# MCU.net
KiCad netlist of a schematic drawn in Altium Designer
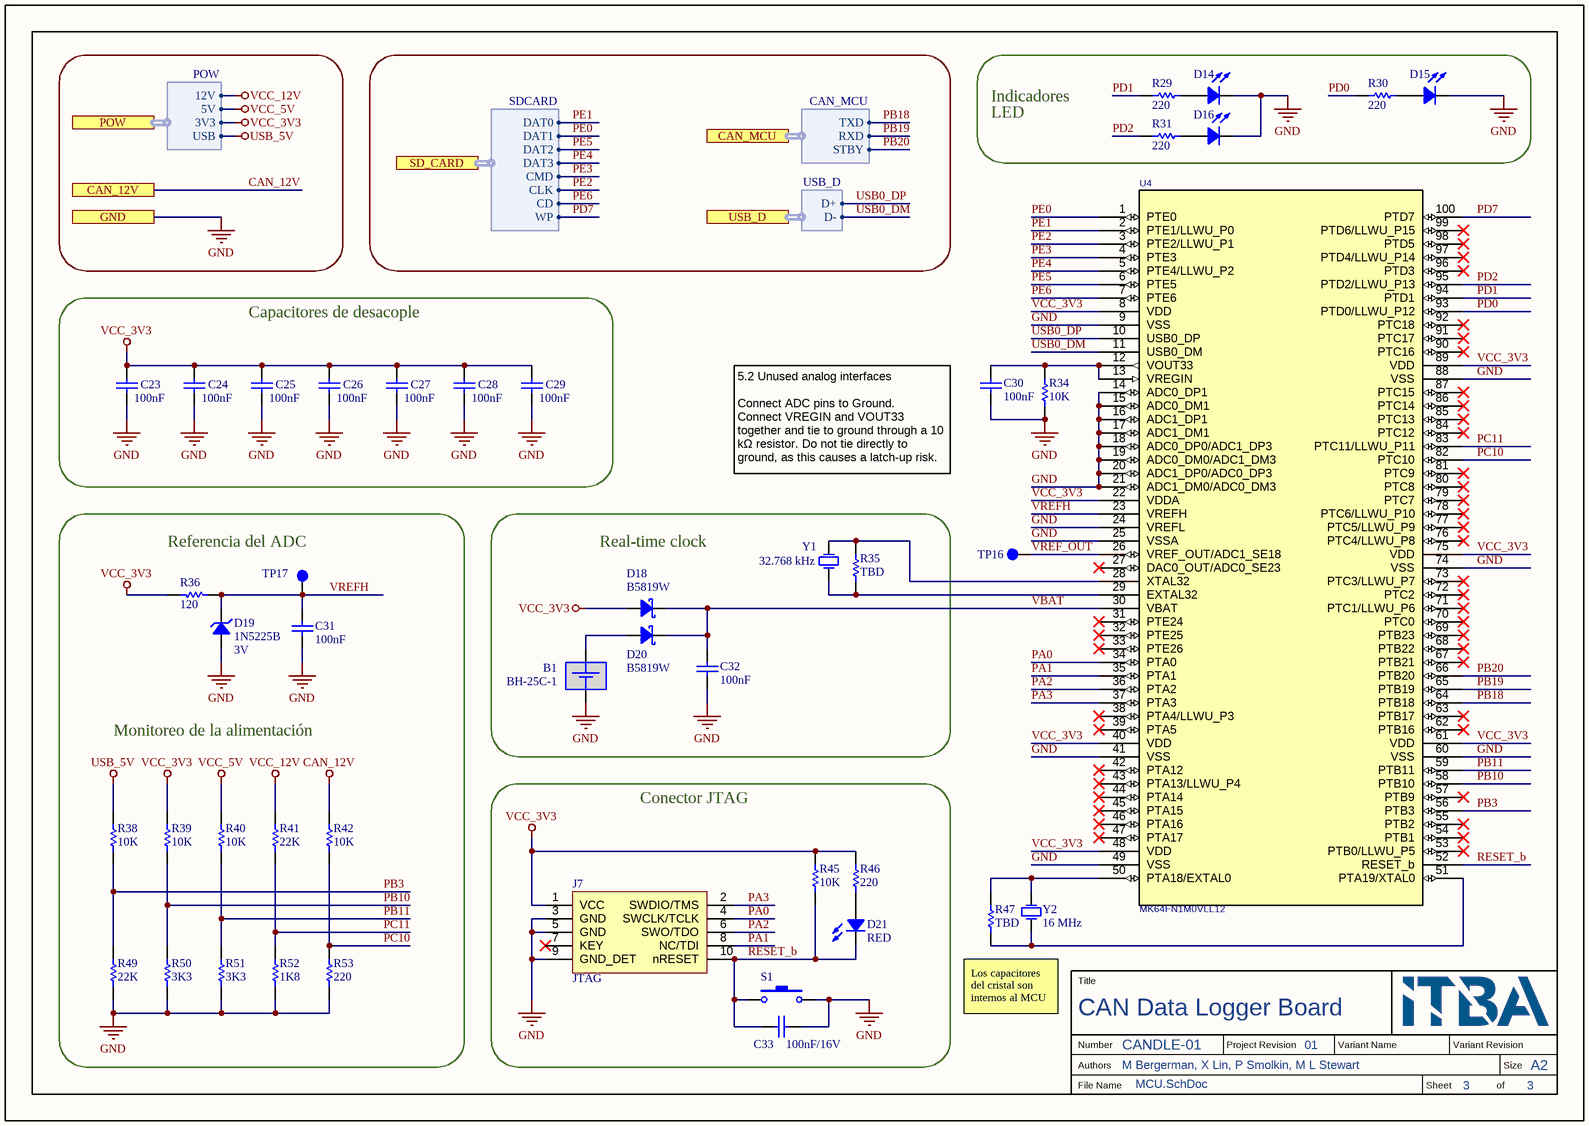
[diagram p0: MCU.SchDoc]

(export (version "E")
  (design (tool "Eeschema 10.0.6"))
  (components
    (comp (ref "B1")
      (value "BH-25C-1")
      (footprint "COIN_CELL_HOLDER")
      (description "Battery Holder")
      (libsource (lib "CANDLE-LIB") (part "Battery Holder"))
    )
    (comp (ref "C23")
      (value "100nF")
      (footprint "CAP0805")
      (description "SMD 0805 Capacitor")
      (libsource (lib "CANDLE-LIB") (part "Capacitor"))
    )
    (comp (ref "C24")
      (value "100nF")
      (footprint "CAP0805")
      (description "SMD 0805 Capacitor")
      (libsource (lib "CANDLE-LIB") (part "Capacitor"))
    )
    (comp (ref "C25")
      (value "100nF")
      (footprint "CAP0805")
      (description "SMD 0805 Capacitor")
      (libsource (lib "CANDLE-LIB") (part "Capacitor"))
    )
    (comp (ref "C26")
      (value "100nF")
      (footprint "CAP0805")
      (description "SMD 0805 Capacitor")
      (libsource (lib "CANDLE-LIB") (part "Capacitor"))
    )
    (comp (ref "C27")
      (value "100nF")
      (footprint "CAP0805")
      (description "SMD 0805 Capacitor")
      (libsource (lib "CANDLE-LIB") (part "Capacitor"))
    )
    (comp (ref "C28")
      (value "100nF")
      (footprint "CAP0805")
      (description "SMD 0805 Capacitor")
      (libsource (lib "CANDLE-LIB") (part "Capacitor"))
    )
    (comp (ref "C29")
      (value "100nF")
      (footprint "CAP0805")
      (description "SMD 0805 Capacitor")
      (libsource (lib "CANDLE-LIB") (part "Capacitor"))
    )
    (comp (ref "C30")
      (value "100nF")
      (footprint "CAP0805")
      (description "SMD 0805 Capacitor")
      (libsource (lib "CANDLE-LIB") (part "Capacitor"))
    )
    (comp (ref "C31")
      (value "100nF")
      (footprint "CAP0805")
      (description "SMD 0805 Capacitor")
      (libsource (lib "CANDLE-LIB") (part "Capacitor"))
    )
    (comp (ref "C32")
      (value "100nF")
      (footprint "CAP0805")
      (description "SMD 0805 Capacitor")
      (libsource (lib "CANDLE-LIB") (part "Capacitor"))
    )
    (comp (ref "C33")
      (value "100nF/16V")
      (footprint "CAP0805")
      (description "SMD 0805 Capacitor")
      (libsource (lib "CANDLE-LIB") (part "Capacitor"))
    )
    (comp (ref "D14")
      (value "RED")
      (footprint "LED-3MM-RED-RA")
      (description "Red 3mm LED")
      (libsource (lib "CANDLE-LIB") (part "LED 3mm Red RA"))
    )
    (comp (ref "D15")
      (value "RED")
      (footprint "LED-3MM-RED-RA")
      (description "Red 3mm LED")
      (libsource (lib "CANDLE-LIB") (part "LED 3mm Red RA"))
    )
    (comp (ref "D16")
      (value "RED")
      (footprint "LED-3MM-RED-RA")
      (description "Red 3mm LED")
      (libsource (lib "CANDLE-LIB") (part "LED 3mm Red RA"))
    )
    (comp (ref "D18")
      (value "B5819W")
      (footprint "SOD-123")
      (description "Schottky Diode")
      (libsource (lib "CANDLE-LIB") (part "Diode Schottky"))
    )
    (comp (ref "D19")
      (value "1N5225B")
      (footprint "DO-35")
      (description "Zener Diode")
      (fields (field (name "VOLTAGE") "3V"))
      (libsource (lib "CANDLE-LIB") (part "Diode Zener"))
    )
    (comp (ref "D20")
      (value "B5819W")
      (footprint "SOD-123")
      (description "Schottky Diode")
      (libsource (lib "CANDLE-LIB") (part "Diode Schottky"))
    )
    (comp (ref "D21")
      (value "RED")
      (footprint "LED-3MM-RED-RA")
      (description "Red 3mm LED")
      (libsource (lib "CANDLE-LIB") (part "LED 3mm Red RA"))
    )
    (comp (ref "J7")
      (value "JTAG")
      (footprint "JTAG-10PIN")
      (description "JTAG header")
      (libsource (lib "CANDLE-LIB") (part "JTAG Header"))
    )
    (comp (ref "R29")
      (value "220")
      (footprint "RES0805")
      (description "SMD 0805 Resistor")
      (libsource (lib "CANDLE-LIB") (part "Resistor"))
    )
    (comp (ref "R30")
      (value "220")
      (footprint "RES0805")
      (description "SMD 0805 Resistor")
      (libsource (lib "CANDLE-LIB") (part "Resistor"))
    )
    (comp (ref "R31")
      (value "220")
      (footprint "RES0805")
      (description "SMD 0805 Resistor")
      (libsource (lib "CANDLE-LIB") (part "Resistor"))
    )
    (comp (ref "R34")
      (value "10K")
      (footprint "RES0805")
      (description "SMD 0805 Resistor")
      (libsource (lib "CANDLE-LIB") (part "Resistor"))
    )
    (comp (ref "R35")
      (value "TBD")
      (footprint "RES0805")
      (description "SMD 0805 Resistor")
      (libsource (lib "CANDLE-LIB") (part "Resistor"))
    )
    (comp (ref "R36")
      (value "120")
      (footprint "RES0805")
      (description "SMD 0805 Resistor")
      (libsource (lib "CANDLE-LIB") (part "Resistor"))
    )
    (comp (ref "R38")
      (value "10K")
      (footprint "RES0805")
      (description "SMD 0805 Resistor")
      (libsource (lib "CANDLE-LIB") (part "Resistor"))
    )
    (comp (ref "R39")
      (value "10K")
      (footprint "RES0805")
      (description "SMD 0805 Resistor")
      (libsource (lib "CANDLE-LIB") (part "Resistor"))
    )
    (comp (ref "R40")
      (value "10K")
      (footprint "RES0805")
      (description "SMD 0805 Resistor")
      (libsource (lib "CANDLE-LIB") (part "Resistor"))
    )
    (comp (ref "R41")
      (value "22K")
      (footprint "RES0805")
      (description "SMD 0805 Resistor")
      (libsource (lib "CANDLE-LIB") (part "Resistor"))
    )
    (comp (ref "R42")
      (value "10K")
      (footprint "RES0805")
      (description "SMD 0805 Resistor")
      (libsource (lib "CANDLE-LIB") (part "Resistor"))
    )
    (comp (ref "R45")
      (value "10K")
      (footprint "RES0805")
      (description "SMD 0805 Resistor")
      (libsource (lib "CANDLE-LIB") (part "Resistor"))
    )
    (comp (ref "R46")
      (value "220")
      (footprint "RES0805")
      (description "SMD 0805 Resistor")
      (libsource (lib "CANDLE-LIB") (part "Resistor"))
    )
    (comp (ref "R47")
      (value "TBD")
      (footprint "RES0805")
      (description "SMD 0805 Resistor")
      (libsource (lib "CANDLE-LIB") (part "Resistor"))
    )
    (comp (ref "R49")
      (value "22K")
      (footprint "RES0805")
      (description "SMD 0805 Resistor")
      (libsource (lib "CANDLE-LIB") (part "Resistor"))
    )
    (comp (ref "R50")
      (value "3K3")
      (footprint "RES0805")
      (description "SMD 0805 Resistor")
      (libsource (lib "CANDLE-LIB") (part "Resistor"))
    )
    (comp (ref "R51")
      (value "3K3")
      (footprint "RES0805")
      (description "SMD 0805 Resistor")
      (libsource (lib "CANDLE-LIB") (part "Resistor"))
    )
    (comp (ref "R52")
      (value "1K8")
      (footprint "RES0805")
      (description "SMD 0805 Resistor")
      (libsource (lib "CANDLE-LIB") (part "Resistor"))
    )
    (comp (ref "R53")
      (value "220")
      (footprint "RES0805")
      (description "SMD 0805 Resistor")
      (libsource (lib "CANDLE-LIB") (part "Resistor"))
    )
    (comp (ref "S1")
      (value "Tact Switch")
      (footprint "TACT SWITCH")
      (description "2-pin 6mm tactile switch (push-button)")
      (fields (field (name "PUBLISHER") "Altium Limited"))
      (libsource (lib "CANDLE-LIB") (part "Tactile Switch"))
    )
    (comp (ref "TP16")
      (value "Testpoint")
      (footprint "TP_SMD_Ø1.0mm")
      (libsource (lib "CANDLE-LIB") (part "Testpoint"))
    )
    (comp (ref "TP17")
      (value "Testpoint")
      (footprint "TP_SMD_Ø1.0mm")
      (libsource (lib "CANDLE-LIB") (part "Testpoint"))
    )
    (comp (ref "U4")
      (value "MK64FN1M0VLL12")
      (footprint "QFP50P1600X1600X160-100N")
      (description "120 MHz ARM Cortex®-M4-based Microcontroller with FPU")
      (fields (field (name "MFG") "NXP") (field (name "FOOTPRINT CHECKED") "Assign OK, Footprint OK"))
      (libsource (lib "CANDLE-LIB") (part "MK64FN1M0VLL12_1"))
    )
    (comp (ref "Y1")
      (value "32.768 kHz")
      (footprint "XTAL-RAD-3X8")
      (description "Crystal Oscillator - Radial 3x8mm")
      (libsource (lib "CANDLE-LIB") (part "Crystal 32.768 kHz"))
    )
    (comp (ref "Y2")
      (value "16 MHz")
      (footprint "XTAL-HC-49S")
      (description "Crystal Oscillator HS-49S")
      (fields (field (name "PUBLISHER") "Altium Limited"))
      (libsource (lib "CANDLE-LIB") (part "Crystal 16 MHz"))
    )
  )
  (nets
    (net (code "5") (name "/PA0") (class "Default")
      (node (ref "J7") (pin "4") (pinfunction "SWCLK/TCLK_4") (pintype "passive"))
      (node (ref "U4") (pin "34") (pinfunction "PTA0_34") (pintype "bidirectional"))
    )
    (net (code "6") (name "/PA1") (class "Default")
      (node (ref "J7") (pin "8") (pinfunction "NC/TDI_8") (pintype "passive"))
      (node (ref "U4") (pin "35") (pinfunction "PTA1_35") (pintype "bidirectional"))
    )
    (net (code "7") (name "/PA2") (class "Default")
      (node (ref "J7") (pin "6") (pinfunction "SWO/TDO_6") (pintype "passive"))
      (node (ref "U4") (pin "36") (pinfunction "PTA2_36") (pintype "bidirectional"))
    )
    (net (code "8") (name "/PA3") (class "Default")
      (node (ref "J7") (pin "2") (pinfunction "SWDIO/TMS_2") (pintype "passive"))
      (node (ref "U4") (pin "37") (pinfunction "PTA3_37") (pintype "bidirectional"))
    )
    (net (code "9") (name "/PB3") (class "Default")
      (node (ref "R38") (pin "2") (pinfunction "2_2") (pintype "passive"))
      (node (ref "R49") (pin "1") (pinfunction "1_1") (pintype "passive"))
      (node (ref "U4") (pin "56") (pinfunction "PTB3_56") (pintype "bidirectional"))
    )
    (net (code "10") (name "/PB10") (class "Default")
      (node (ref "R39") (pin "2") (pinfunction "2_2") (pintype "passive"))
      (node (ref "R50") (pin "1") (pinfunction "1_1") (pintype "passive"))
      (node (ref "U4") (pin "58") (pinfunction "PTB10_58") (pintype "bidirectional"))
    )
    (net (code "11") (name "/PB11") (class "Default")
      (node (ref "R40") (pin "2") (pinfunction "2_2") (pintype "passive"))
      (node (ref "R51") (pin "1") (pinfunction "1_1") (pintype "passive"))
      (node (ref "U4") (pin "59") (pinfunction "PTB11_59") (pintype "bidirectional"))
    )
    (net (code "12") (name "/PB18") (class "Default")
      (node (ref "U4") (pin "64") (pinfunction "PTB18_64") (pintype "bidirectional"))
    )
    (net (code "13") (name "/PB19") (class "Default")
      (node (ref "U4") (pin "65") (pinfunction "PTB19_65") (pintype "bidirectional"))
    )
    (net (code "14") (name "/PB20") (class "Default")
      (node (ref "U4") (pin "66") (pinfunction "PTB20_66") (pintype "bidirectional"))
    )
    (net (code "15") (name "/PC10") (class "Default")
      (node (ref "R42") (pin "2") (pinfunction "2_2") (pintype "passive"))
      (node (ref "R53") (pin "1") (pinfunction "1_1") (pintype "passive"))
      (node (ref "U4") (pin "82") (pinfunction "PTC10_82") (pintype "bidirectional"))
    )
    (net (code "16") (name "/PC11") (class "Default")
      (node (ref "R41") (pin "2") (pinfunction "2_2") (pintype "passive"))
      (node (ref "R52") (pin "1") (pinfunction "1_1") (pintype "passive"))
      (node (ref "U4") (pin "83") (pinfunction "PTC11/LLWU_P11_83") (pintype "bidirectional"))
    )
    (net (code "17") (name "/PD0") (class "Default")
      (node (ref "R30") (pin "1") (pinfunction "1_1") (pintype "passive"))
      (node (ref "U4") (pin "93") (pinfunction "PTD0/LLWU_P12_93") (pintype "bidirectional"))
    )
    (net (code "18") (name "/PD1") (class "Default")
      (node (ref "R29") (pin "1") (pinfunction "1_1") (pintype "passive"))
      (node (ref "U4") (pin "94") (pinfunction "PTD1_94") (pintype "bidirectional"))
    )
    (net (code "19") (name "/PD2") (class "Default")
      (node (ref "R31") (pin "1") (pinfunction "1_1") (pintype "passive"))
      (node (ref "U4") (pin "95") (pinfunction "PTD2/LLWU_P13_95") (pintype "bidirectional"))
    )
    (net (code "20") (name "/PD7") (class "Default")
      (node (ref "U4") (pin "100") (pinfunction "PTD7_100") (pintype "bidirectional"))
    )
    (net (code "21") (name "/PE0") (class "Default")
      (node (ref "U4") (pin "1") (pinfunction "PTE0_1") (pintype "bidirectional"))
    )
    (net (code "22") (name "/PE1") (class "Default")
      (node (ref "U4") (pin "2") (pinfunction "PTE1/LLWU_P0_2") (pintype "bidirectional"))
    )
    (net (code "23") (name "/PE2") (class "Default")
      (node (ref "U4") (pin "3") (pinfunction "PTE2/LLWU_P1_3") (pintype "bidirectional"))
    )
    (net (code "24") (name "/PE3") (class "Default")
      (node (ref "U4") (pin "4") (pinfunction "PTE3_4") (pintype "bidirectional"))
    )
    (net (code "25") (name "/PE4") (class "Default")
      (node (ref "U4") (pin "5") (pinfunction "PTE4/LLWU_P2_5") (pintype "bidirectional"))
    )
    (net (code "26") (name "/PE5") (class "Default")
      (node (ref "U4") (pin "6") (pinfunction "PTE5_6") (pintype "bidirectional"))
    )
    (net (code "27") (name "/PE6") (class "Default")
      (node (ref "U4") (pin "7") (pinfunction "PTE6_7") (pintype "bidirectional"))
    )
    (net (code "28") (name "/RESET_b") (class "Default")
      (node (ref "C33") (pin "2") (pinfunction "2_2") (pintype "passive"))
      (node (ref "D21") (pin "2") (pinfunction "K_2") (pintype "passive"))
      (node (ref "J7") (pin "10") (pinfunction "nRESET_10") (pintype "passive"))
      (node (ref "R45") (pin "1") (pinfunction "1_1") (pintype "passive"))
      (node (ref "S1") (pin "1") (pinfunction "1_1") (pintype "passive"))
      (node (ref "U4") (pin "52") (pinfunction "RESET_b_52") (pintype "passive"))
    )
    (net (code "29") (name "/USB0_DM") (class "Default")
      (node (ref "U4") (pin "11") (pinfunction "USB0_DM_11") (pintype "passive"))
    )
    (net (code "30") (name "/USB0_DP") (class "Default")
      (node (ref "U4") (pin "10") (pinfunction "USB0_DP_10") (pintype "passive"))
    )
    (net (code "31") (name "/VBAT") (class "Default")
      (node (ref "C32") (pin "2") (pinfunction "2_2") (pintype "passive"))
      (node (ref "D18") (pin "2") (pinfunction "K_2") (pintype "passive"))
      (node (ref "D20") (pin "2") (pinfunction "K_2") (pintype "passive"))
      (node (ref "U4") (pin "30") (pinfunction "VBAT_30") (pintype "power_in"))
    )
    (net (code "32") (name "/VREFH") (class "Default")
      (node (ref "C31") (pin "2") (pinfunction "2_2") (pintype "passive"))
      (node (ref "D19") (pin "1") (pinfunction "K_1") (pintype "passive"))
      (node (ref "R36") (pin "1") (pinfunction "1_1") (pintype "passive"))
      (node (ref "TP17") (pin "1") (pinfunction "TP_1") (pintype "passive"))
      (node (ref "U4") (pin "23") (pinfunction "VREFH_23") (pintype "power_in"))
    )
    (net (code "33") (name "/VREF_OUT") (class "Default")
      (node (ref "TP16") (pin "1") (pinfunction "TP_1") (pintype "passive"))
      (node (ref "U4") (pin "26") (pinfunction "VREF_OUT/ADC1_SE18_26") (pintype "bidirectional"))
    )
    (net (code "38") (name "CAN_12V") (class "Default")
      (node (ref "R42") (pin "1") (pinfunction "1_1") (pintype "passive"))
    )
    (net (code "39") (name "GND") (class "Default")
      (node (ref "B1") (pin "2") (pinfunction "2_2") (pintype "passive"))
      (node (ref "C23") (pin "1") (pinfunction "1_1") (pintype "passive"))
      (node (ref "C24") (pin "1") (pinfunction "1_1") (pintype "passive"))
      (node (ref "C25") (pin "1") (pinfunction "1_1") (pintype "passive"))
      (node (ref "C26") (pin "1") (pinfunction "1_1") (pintype "passive"))
      (node (ref "C27") (pin "1") (pinfunction "1_1") (pintype "passive"))
      (node (ref "C28") (pin "1") (pinfunction "1_1") (pintype "passive"))
      (node (ref "C29") (pin "1") (pinfunction "1_1") (pintype "passive"))
      (node (ref "C30") (pin "1") (pinfunction "1_1") (pintype "passive"))
      (node (ref "C31") (pin "1") (pinfunction "1_1") (pintype "passive"))
      (node (ref "C32") (pin "1") (pinfunction "1_1") (pintype "passive"))
      (node (ref "C33") (pin "1") (pinfunction "1_1") (pintype "passive"))
      (node (ref "D14") (pin "2") (pinfunction "K_2") (pintype "passive"))
      (node (ref "D15") (pin "2") (pinfunction "K_2") (pintype "passive"))
      (node (ref "D16") (pin "2") (pinfunction "K_2") (pintype "passive"))
      (node (ref "D19") (pin "2") (pinfunction "A_2") (pintype "passive"))
      (node (ref "J7") (pin "3") (pinfunction "GND_3") (pintype "passive"))
      (node (ref "J7") (pin "5") (pinfunction "GND_5") (pintype "passive"))
      (node (ref "J7") (pin "9") (pinfunction "GND_DET_9") (pintype "passive"))
      (node (ref "R34") (pin "1") (pinfunction "1_1") (pintype "passive"))
      (node (ref "R49") (pin "2") (pinfunction "2_2") (pintype "passive"))
      (node (ref "R50") (pin "2") (pinfunction "2_2") (pintype "passive"))
      (node (ref "R51") (pin "2") (pinfunction "2_2") (pintype "passive"))
      (node (ref "R52") (pin "2") (pinfunction "2_2") (pintype "passive"))
      (node (ref "R53") (pin "2") (pinfunction "2_2") (pintype "passive"))
      (node (ref "S1") (pin "2") (pinfunction "2_2") (pintype "passive"))
      (node (ref "U4") (pin "14") (pinfunction "ADC0_DP1_14") (pintype "bidirectional"))
      (node (ref "U4") (pin "15") (pinfunction "ADC0_DM1_15") (pintype "bidirectional"))
      (node (ref "U4") (pin "16") (pinfunction "ADC1_DP1_16") (pintype "bidirectional"))
      (node (ref "U4") (pin "17") (pinfunction "ADC1_DM1_17") (pintype "bidirectional"))
      (node (ref "U4") (pin "18") (pinfunction "ADC0_DP0/ADC1_DP3_18") (pintype "bidirectional"))
      (node (ref "U4") (pin "19") (pinfunction "ADC0_DM0/ADC1_DM3_19") (pintype "bidirectional"))
      (node (ref "U4") (pin "20") (pinfunction "ADC1_DP0/ADC0_DP3_20") (pintype "bidirectional"))
      (node (ref "U4") (pin "21") (pinfunction "ADC1_DM0/ADC0_DM3_21") (pintype "bidirectional"))
      (node (ref "U4") (pin "24") (pinfunction "VREFL_24") (pintype "power_in"))
      (node (ref "U4") (pin "25") (pinfunction "VSSA_25") (pintype "power_in"))
      (node (ref "U4") (pin "41") (pinfunction "VSS_41") (pintype "power_in"))
      (node (ref "U4") (pin "49") (pinfunction "VSS_49") (pintype "power_in"))
      (node (ref "U4") (pin "60") (pinfunction "VSS_60") (pintype "power_in"))
      (node (ref "U4") (pin "74") (pinfunction "VSS_74") (pintype "power_in"))
      (node (ref "U4") (pin "88") (pinfunction "VSS_88") (pintype "power_in"))
      (node (ref "U4") (pin "9") (pinfunction "VSS_9") (pintype "power_in"))
    )
    (net (code "40") (name "Net-(D14-A)") (class "Default")
      (node (ref "D14") (pin "1") (pinfunction "A_1") (pintype "passive"))
      (node (ref "R29") (pin "2") (pinfunction "2_2") (pintype "passive"))
    )
    (net (code "41") (name "Net-(D15-A)") (class "Default")
      (node (ref "D15") (pin "1") (pinfunction "A_1") (pintype "passive"))
      (node (ref "R30") (pin "2") (pinfunction "2_2") (pintype "passive"))
    )
    (net (code "42") (name "Net-(D16-A)") (class "Default")
      (node (ref "D16") (pin "1") (pinfunction "A_1") (pintype "passive"))
      (node (ref "R31") (pin "2") (pinfunction "2_2") (pintype "passive"))
    )
    (net (code "43") (name "Net-(D20-A)") (class "Default")
      (node (ref "B1") (pin "1") (pinfunction "1_1") (pintype "passive"))
      (node (ref "D20") (pin "1") (pinfunction "A_1") (pintype "passive"))
    )
    (net (code "44") (name "Net-(D21-A)") (class "Default")
      (node (ref "D21") (pin "1") (pinfunction "A_1") (pintype "passive"))
      (node (ref "R46") (pin "2") (pinfunction "2_2") (pintype "passive"))
    )
    (net (code "45") (name "Net-(U4-EXTAL32)") (class "Default")
      (node (ref "R35") (pin "2") (pinfunction "2_2") (pintype "passive"))
      (node (ref "U4") (pin "29") (pinfunction "EXTAL32_29") (pintype "passive"))
      (node (ref "Y1") (pin "1") (pinfunction "OSC1_1") (pintype "passive"))
    )
    (net (code "46") (name "Net-(U4-PTA18{slash}EXTAL0)") (class "Default")
      (node (ref "R47") (pin "2") (pinfunction "2_2") (pintype "passive"))
      (node (ref "U4") (pin "50") (pinfunction "PTA18/EXTAL0_50") (pintype "bidirectional"))
      (node (ref "Y2") (pin "2") (pinfunction "OSC2_2") (pintype "passive"))
    )
    (net (code "47") (name "Net-(U4-PTA19{slash}XTAL0)") (class "Default")
      (node (ref "R47") (pin "1") (pinfunction "1_1") (pintype "passive"))
      (node (ref "U4") (pin "51") (pinfunction "PTA19/XTAL0_51") (pintype "bidirectional"))
      (node (ref "Y2") (pin "1") (pinfunction "OSC1_1") (pintype "passive"))
    )
    (net (code "48") (name "Net-(U4-VOUT33)") (class "Default")
      (node (ref "C30") (pin "2") (pinfunction "2_2") (pintype "passive"))
      (node (ref "R34") (pin "2") (pinfunction "2_2") (pintype "passive"))
      (node (ref "U4") (pin "12") (pinfunction "VOUT33_12") (pintype "output"))
      (node (ref "U4") (pin "13") (pinfunction "VREGIN_13") (pintype "input"))
    )
    (net (code "49") (name "Net-(U4-XTAL32)") (class "Default")
      (node (ref "R35") (pin "1") (pinfunction "1_1") (pintype "passive"))
      (node (ref "U4") (pin "28") (pinfunction "XTAL32_28") (pintype "passive"))
      (node (ref "Y1") (pin "2") (pinfunction "OSC2_2") (pintype "passive"))
    )
    (net (code "50") (name "USB_5V") (class "Default")
      (node (ref "R38") (pin "1") (pinfunction "1_1") (pintype "passive"))
    )
    (net (code "51") (name "VCC_3V3") (class "Default")
      (node (ref "C23") (pin "2") (pinfunction "2_2") (pintype "passive"))
      (node (ref "C24") (pin "2") (pinfunction "2_2") (pintype "passive"))
      (node (ref "C25") (pin "2") (pinfunction "2_2") (pintype "passive"))
      (node (ref "C26") (pin "2") (pinfunction "2_2") (pintype "passive"))
      (node (ref "C27") (pin "2") (pinfunction "2_2") (pintype "passive"))
      (node (ref "C28") (pin "2") (pinfunction "2_2") (pintype "passive"))
      (node (ref "C29") (pin "2") (pinfunction "2_2") (pintype "passive"))
      (node (ref "D18") (pin "1") (pinfunction "A_1") (pintype "passive"))
      (node (ref "J7") (pin "1") (pinfunction "VCC_1") (pintype "passive"))
      (node (ref "R36") (pin "2") (pinfunction "2_2") (pintype "passive"))
      (node (ref "R39") (pin "1") (pinfunction "1_1") (pintype "passive"))
      (node (ref "R45") (pin "2") (pinfunction "2_2") (pintype "passive"))
      (node (ref "R46") (pin "1") (pinfunction "1_1") (pintype "passive"))
      (node (ref "U4") (pin "22") (pinfunction "VDDA_22") (pintype "power_in"))
      (node (ref "U4") (pin "40") (pinfunction "VDD_40") (pintype "power_in"))
      (node (ref "U4") (pin "48") (pinfunction "VDD_48") (pintype "power_in"))
      (node (ref "U4") (pin "61") (pinfunction "VDD_61") (pintype "power_in"))
      (node (ref "U4") (pin "75") (pinfunction "VDD_75") (pintype "power_in"))
      (node (ref "U4") (pin "8") (pinfunction "VDD_8") (pintype "power_in"))
      (node (ref "U4") (pin "89") (pinfunction "VDD_89") (pintype "power_in"))
    )
    (net (code "52") (name "VCC_5V") (class "Default")
      (node (ref "R40") (pin "1") (pinfunction "1_1") (pintype "passive"))
    )
    (net (code "53") (name "VCC_12V") (class "Default")
      (node (ref "R41") (pin "1") (pinfunction "1_1") (pintype "passive"))
    )
    (net (code "54") (name "unconnected-(J7-KEY-Pad7)") (class "Default")
      (node (ref "J7") (pin "7") (pinfunction "KEY_7") (pintype "passive+no_connect"))
    )
    (net (code "55") (name "unconnected-(U4-DAC0_OUT{slash}ADC0_SE23-Pad27)") (class "Default")
      (node (ref "U4") (pin "27") (pinfunction "DAC0_OUT/ADC0_SE23_27") (pintype "bidirectional+no_connect"))
    )
    (net (code "56") (name "unconnected-(U4-PTA4{slash}LLWU_P3-Pad38)") (class "Default")
      (node (ref "U4") (pin "38") (pinfunction "PTA4/LLWU_P3_38") (pintype "bidirectional+no_connect"))
    )
    (net (code "57") (name "unconnected-(U4-PTA5-Pad39)") (class "Default")
      (node (ref "U4") (pin "39") (pinfunction "PTA5_39") (pintype "bidirectional+no_connect"))
    )
    (net (code "58") (name "unconnected-(U4-PTA12-Pad42)") (class "Default")
      (node (ref "U4") (pin "42") (pinfunction "PTA12_42") (pintype "bidirectional+no_connect"))
    )
    (net (code "59") (name "unconnected-(U4-PTA13{slash}LLWU_P4-Pad43)") (class "Default")
      (node (ref "U4") (pin "43") (pinfunction "PTA13/LLWU_P4_43") (pintype "bidirectional+no_connect"))
    )
    (net (code "60") (name "unconnected-(U4-PTA14-Pad44)") (class "Default")
      (node (ref "U4") (pin "44") (pinfunction "PTA14_44") (pintype "bidirectional+no_connect"))
    )
    (net (code "61") (name "unconnected-(U4-PTA15-Pad45)") (class "Default")
      (node (ref "U4") (pin "45") (pinfunction "PTA15_45") (pintype "bidirectional+no_connect"))
    )
    (net (code "62") (name "unconnected-(U4-PTA16-Pad46)") (class "Default")
      (node (ref "U4") (pin "46") (pinfunction "PTA16_46") (pintype "bidirectional+no_connect"))
    )
    (net (code "63") (name "unconnected-(U4-PTA17-Pad47)") (class "Default")
      (node (ref "U4") (pin "47") (pinfunction "PTA17_47") (pintype "bidirectional+no_connect"))
    )
    (net (code "64") (name "unconnected-(U4-PTB0{slash}LLWU_P5-Pad53)") (class "Default")
      (node (ref "U4") (pin "53") (pinfunction "PTB0/LLWU_P5_53") (pintype "bidirectional+no_connect"))
    )
    (net (code "65") (name "unconnected-(U4-PTB1-Pad54)") (class "Default")
      (node (ref "U4") (pin "54") (pinfunction "PTB1_54") (pintype "bidirectional+no_connect"))
    )
    (net (code "66") (name "unconnected-(U4-PTB2-Pad55)") (class "Default")
      (node (ref "U4") (pin "55") (pinfunction "PTB2_55") (pintype "bidirectional+no_connect"))
    )
    (net (code "67") (name "unconnected-(U4-PTB9-Pad57)") (class "Default")
      (node (ref "U4") (pin "57") (pinfunction "PTB9_57") (pintype "bidirectional+no_connect"))
    )
    (net (code "68") (name "unconnected-(U4-PTB16-Pad62)") (class "Default")
      (node (ref "U4") (pin "62") (pinfunction "PTB16_62") (pintype "bidirectional+no_connect"))
    )
    (net (code "69") (name "unconnected-(U4-PTB17-Pad63)") (class "Default")
      (node (ref "U4") (pin "63") (pinfunction "PTB17_63") (pintype "bidirectional+no_connect"))
    )
    (net (code "70") (name "unconnected-(U4-PTB21-Pad67)") (class "Default")
      (node (ref "U4") (pin "67") (pinfunction "PTB21_67") (pintype "bidirectional+no_connect"))
    )
    (net (code "71") (name "unconnected-(U4-PTB22-Pad68)") (class "Default")
      (node (ref "U4") (pin "68") (pinfunction "PTB22_68") (pintype "bidirectional+no_connect"))
    )
    (net (code "72") (name "unconnected-(U4-PTB23-Pad69)") (class "Default")
      (node (ref "U4") (pin "69") (pinfunction "PTB23_69") (pintype "bidirectional+no_connect"))
    )
    (net (code "73") (name "unconnected-(U4-PTC0-Pad70)") (class "Default")
      (node (ref "U4") (pin "70") (pinfunction "PTC0_70") (pintype "bidirectional+no_connect"))
    )
    (net (code "74") (name "unconnected-(U4-PTC1{slash}LLWU_P6-Pad71)") (class "Default")
      (node (ref "U4") (pin "71") (pinfunction "PTC1/LLWU_P6_71") (pintype "bidirectional+no_connect"))
    )
    (net (code "75") (name "unconnected-(U4-PTC2-Pad72)") (class "Default")
      (node (ref "U4") (pin "72") (pinfunction "PTC2_72") (pintype "bidirectional+no_connect"))
    )
    (net (code "76") (name "unconnected-(U4-PTC3{slash}LLWU_P7-Pad73)") (class "Default")
      (node (ref "U4") (pin "73") (pinfunction "PTC3/LLWU_P7_73") (pintype "bidirectional+no_connect"))
    )
    (net (code "77") (name "unconnected-(U4-PTC4{slash}LLWU_P8-Pad76)") (class "Default")
      (node (ref "U4") (pin "76") (pinfunction "PTC4/LLWU_P8_76") (pintype "bidirectional+no_connect"))
    )
    (net (code "78") (name "unconnected-(U4-PTC5{slash}LLWU_P9-Pad77)") (class "Default")
      (node (ref "U4") (pin "77") (pinfunction "PTC5/LLWU_P9_77") (pintype "bidirectional+no_connect"))
    )
    (net (code "79") (name "unconnected-(U4-PTC6{slash}LLWU_P10-Pad78)") (class "Default")
      (node (ref "U4") (pin "78") (pinfunction "PTC6/LLWU_P10_78") (pintype "bidirectional+no_connect"))
    )
    (net (code "80") (name "unconnected-(U4-PTC7-Pad79)") (class "Default")
      (node (ref "U4") (pin "79") (pinfunction "PTC7_79") (pintype "bidirectional+no_connect"))
    )
    (net (code "81") (name "unconnected-(U4-PTC8-Pad80)") (class "Default")
      (node (ref "U4") (pin "80") (pinfunction "PTC8_80") (pintype "bidirectional+no_connect"))
    )
    (net (code "82") (name "unconnected-(U4-PTC9-Pad81)") (class "Default")
      (node (ref "U4") (pin "81") (pinfunction "PTC9_81") (pintype "bidirectional+no_connect"))
    )
    (net (code "83") (name "unconnected-(U4-PTC12-Pad84)") (class "Default")
      (node (ref "U4") (pin "84") (pinfunction "PTC12_84") (pintype "bidirectional+no_connect"))
    )
    (net (code "84") (name "unconnected-(U4-PTC13-Pad85)") (class "Default")
      (node (ref "U4") (pin "85") (pinfunction "PTC13_85") (pintype "bidirectional+no_connect"))
    )
    (net (code "85") (name "unconnected-(U4-PTC14-Pad86)") (class "Default")
      (node (ref "U4") (pin "86") (pinfunction "PTC14_86") (pintype "bidirectional+no_connect"))
    )
    (net (code "86") (name "unconnected-(U4-PTC15-Pad87)") (class "Default")
      (node (ref "U4") (pin "87") (pinfunction "PTC15_87") (pintype "bidirectional+no_connect"))
    )
    (net (code "87") (name "unconnected-(U4-PTC16-Pad90)") (class "Default")
      (node (ref "U4") (pin "90") (pinfunction "PTC16_90") (pintype "bidirectional+no_connect"))
    )
    (net (code "88") (name "unconnected-(U4-PTC17-Pad91)") (class "Default")
      (node (ref "U4") (pin "91") (pinfunction "PTC17_91") (pintype "bidirectional+no_connect"))
    )
    (net (code "89") (name "unconnected-(U4-PTC18-Pad92)") (class "Default")
      (node (ref "U4") (pin "92") (pinfunction "PTC18_92") (pintype "bidirectional+no_connect"))
    )
    (net (code "90") (name "unconnected-(U4-PTD3-Pad96)") (class "Default")
      (node (ref "U4") (pin "96") (pinfunction "PTD3_96") (pintype "bidirectional+no_connect"))
    )
    (net (code "91") (name "unconnected-(U4-PTD4{slash}LLWU_P14-Pad97)") (class "Default")
      (node (ref "U4") (pin "97") (pinfunction "PTD4/LLWU_P14_97") (pintype "bidirectional+no_connect"))
    )
    (net (code "92") (name "unconnected-(U4-PTD5-Pad98)") (class "Default")
      (node (ref "U4") (pin "98") (pinfunction "PTD5_98") (pintype "bidirectional+no_connect"))
    )
    (net (code "93") (name "unconnected-(U4-PTD6{slash}LLWU_P15-Pad99)") (class "Default")
      (node (ref "U4") (pin "99") (pinfunction "PTD6/LLWU_P15_99") (pintype "bidirectional+no_connect"))
    )
    (net (code "94") (name "unconnected-(U4-PTE24-Pad31)") (class "Default")
      (node (ref "U4") (pin "31") (pinfunction "PTE24_31") (pintype "bidirectional+no_connect"))
    )
    (net (code "95") (name "unconnected-(U4-PTE25-Pad32)") (class "Default")
      (node (ref "U4") (pin "32") (pinfunction "PTE25_32") (pintype "bidirectional+no_connect"))
    )
    (net (code "96") (name "unconnected-(U4-PTE26-Pad33)") (class "Default")
      (node (ref "U4") (pin "33") (pinfunction "PTE26_33") (pintype "bidirectional+no_connect"))
    )
  )
)
